# IWatch_DISP.net
KiCad netlist of a schematic drawn in Altium Designer
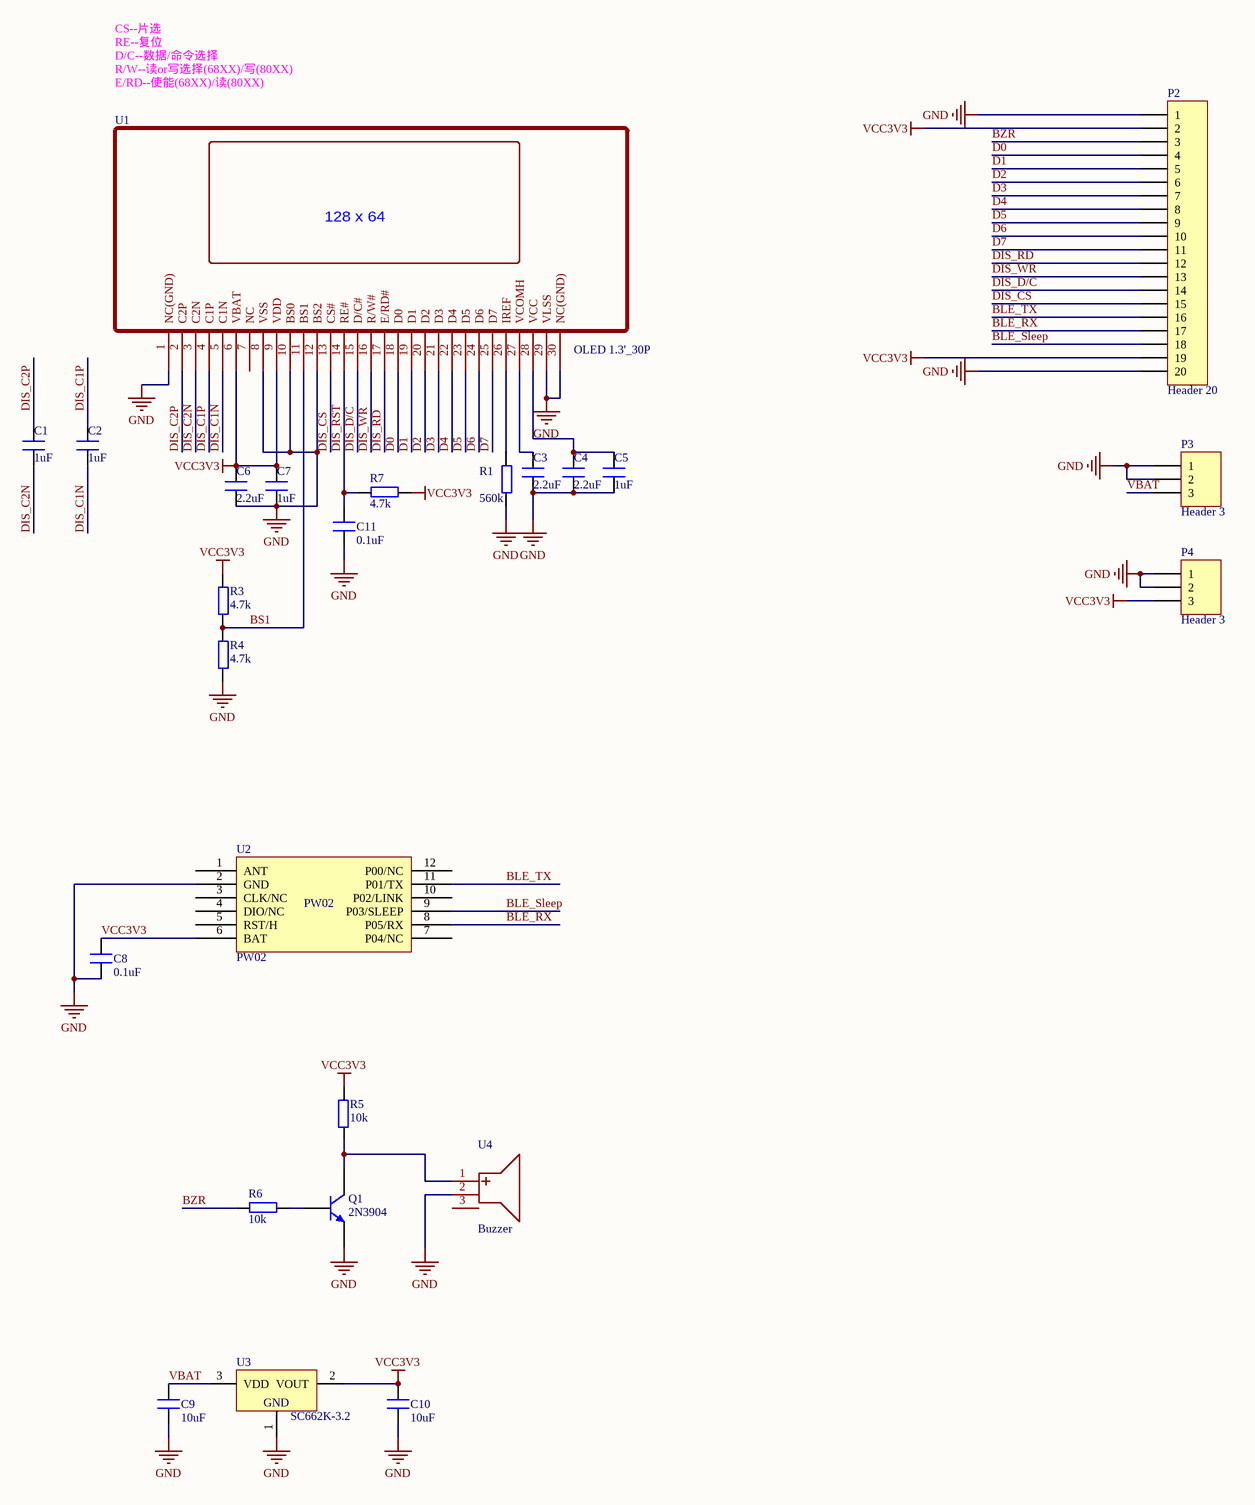
[diagram p0: IWatch_DISP.SchDoc]

(export (version "E")
  (design (tool "Eeschema 10.0.6"))
  (components
    (comp (ref "C1") (value "1uF") (footprint "C0603") (libsource (lib "Explorer STM32F407封装库2") (part "C")))
    (comp (ref "C2") (value "1uF") (footprint "C0603") (libsource (lib "Explorer STM32F407封装库2") (part "C")))
    (comp (ref "C3")
      (value "2.2uF")
      (footprint "C0603")
      (libsource (lib "Explorer STM32F407封装库2") (part "C"))
    )
    (comp (ref "C4")
      (value "2.2uF")
      (footprint "C0603")
      (libsource (lib "Explorer STM32F407封装库2") (part "C"))
    )
    (comp (ref "C5") (value "1uF") (footprint "C0603") (libsource (lib "Explorer STM32F407封装库2") (part "C")))
    (comp (ref "C6")
      (value "2.2uF")
      (footprint "C0603")
      (libsource (lib "Explorer STM32F407封装库2") (part "C"))
    )
    (comp (ref "C7") (value "1uF") (footprint "C0603") (libsource (lib "Explorer STM32F407封装库2") (part "C")))
    (comp (ref "C8")
      (value "0.1uF")
      (footprint "C0603")
      (libsource (lib "Explorer STM32F407封装库2") (part "C"))
    )
    (comp (ref "C9") (value "10uF") (footprint "C0603") (libsource (lib "Explorer STM32F407封装库2") (part "C")))
    (comp (ref "C10")
      (value "10uF")
      (footprint "C0603")
      (libsource (lib "Explorer STM32F407封装库2") (part "C"))
    )
    (comp (ref "C11")
      (value "0.1uF")
      (footprint "C0603")
      (libsource (lib "Explorer STM32F407封装库2") (part "C"))
    )
    (comp (ref "P2")
      (value "Header 20")
      (footprint "HDR_1X20P_1.27MM")
      (description "Header, 20-Pin")
      (fields (field (name "PUBLISHER") "Altium Limited"))
      (libsource (lib "Miscellaneous Connectors") (part "Header 20"))
    )
    (comp (ref "P3")
      (value "Header 3")
      (footprint "HDR_1X3P_1.27MM")
      (description "Header, 3-Pin")
      (fields (field (name "PUBLISHER") "Altium Limited"))
      (libsource (lib "Miscellaneous Connectors") (part "Header 3"))
    )
    (comp (ref "P4")
      (value "Header 3")
      (footprint "HDR_1X3P_1.27MM")
      (description "Header, 3-Pin")
      (fields (field (name "PUBLISHER") "Altium Limited"))
      (libsource (lib "Miscellaneous Connectors") (part "Header 3"))
    )
    (comp (ref "Q1")
      (value "2N3904")
      (footprint "SOT23-3")
      (description "NPN General Purpose Amplifier")
      (fields (field (name "PUBLISHER") "Altium Limited"))
      (libsource (lib "Miscellaneous Devices") (part "2N3904"))
    )
    (comp (ref "R1") (value "560k") (footprint "R0603") (libsource (lib "Explorer STM32F407封装库2") (part "R")))
    (comp (ref "R3") (value "4.7k") (footprint "R0603") (libsource (lib "Explorer STM32F407封装库2") (part "R")))
    (comp (ref "R4") (value "4.7k") (footprint "R0603") (libsource (lib "Explorer STM32F407封装库2") (part "R")))
    (comp (ref "R5") (value "10k") (footprint "R0603") (libsource (lib "Explorer STM32F407封装库2") (part "R")))
    (comp (ref "R6") (value "10k") (footprint "R0603") (libsource (lib "Explorer STM32F407封装库2") (part "R")))
    (comp (ref "R7") (value "4.7k") (footprint "R0603") (libsource (lib "Explorer STM32F407封装库2") (part "R")))
    (comp (ref "U1")
      (value "OLED 1.3'_30P")
      (footprint "OLED 1.3'_30P")
      (description "1.3寸oled显示屏12864 分辨率 驱动芯片ssd1315兼容ssd1306")
      (libsource (lib "TOF_SCH") (part "OLED 1.3'_30P"))
    )
    (comp (ref "U2")
      (value "PW02")
      (footprint "PW02")
      (description "PW02 蓝牙模块 蓝牙5.0 串口透传,DA14585芯片")
      (libsource (lib "IWatch") (part "PW02"))
    )
    (comp (ref "U3")
      (value "SC662K-3.2")
      (footprint "SOT23-3")
      (description "Low Dropout,  250mA")
      (libsource (lib "TOF_SCH") (part "SC662K-3.2"))
    )
    (comp (ref "U4")
      (value "Buzzer")
      (footprint "Buzzer_5.5x2.5mm")
      (libsource (lib "TOF_SCH") (part "Buzzer"))
    )
  )
  (nets
    (net (code "1") (name "/BLE_RX") (class "Default")
      (node (ref "P2") (pin "17") (pinfunction "17_17") (pintype "passive"))
      (node (ref "U2") (pin "8") (pinfunction "P05/RX_8") (pintype "passive"))
    )
    (net (code "2") (name "/BLE_Sleep") (class "Default")
      (node (ref "P2") (pin "18") (pinfunction "18_18") (pintype "passive"))
      (node (ref "U2") (pin "9") (pinfunction "P03/SLEEP_9") (pintype "passive"))
    )
    (net (code "3") (name "/BLE_TX") (class "Default")
      (node (ref "P2") (pin "16") (pinfunction "16_16") (pintype "passive"))
      (node (ref "U2") (pin "11") (pinfunction "P01/TX_11") (pintype "passive"))
    )
    (net (code "4") (name "/BS1") (class "Default")
      (node (ref "R3") (pin "1") (pintype "passive"))
      (node (ref "R4") (pin "2") (pintype "passive"))
      (node (ref "U1") (pin "11") (pinfunction "BS1_11") (pintype "passive"))
    )
    (net (code "5") (name "/BZR") (class "Default")
      (node (ref "P2") (pin "3") (pinfunction "3_3") (pintype "passive"))
      (node (ref "R6") (pin "2") (pintype "passive"))
    )
    (net (code "6") (name "/D0") (class "Default")
      (node (ref "P2") (pin "4") (pinfunction "4_4") (pintype "passive"))
      (node (ref "U1") (pin "18") (pinfunction "D0_18") (pintype "passive"))
    )
    (net (code "7") (name "/D1") (class "Default")
      (node (ref "P2") (pin "5") (pinfunction "5_5") (pintype "passive"))
      (node (ref "U1") (pin "19") (pinfunction "D1_19") (pintype "passive"))
    )
    (net (code "8") (name "/D2") (class "Default")
      (node (ref "P2") (pin "6") (pinfunction "6_6") (pintype "passive"))
      (node (ref "U1") (pin "20") (pinfunction "D2_20") (pintype "passive"))
    )
    (net (code "9") (name "/D3") (class "Default")
      (node (ref "P2") (pin "7") (pinfunction "7_7") (pintype "passive"))
      (node (ref "U1") (pin "21") (pinfunction "D3_21") (pintype "passive"))
    )
    (net (code "10") (name "/D4") (class "Default")
      (node (ref "P2") (pin "8") (pinfunction "8_8") (pintype "passive"))
      (node (ref "U1") (pin "22") (pinfunction "D4_22") (pintype "passive"))
    )
    (net (code "11") (name "/D5") (class "Default")
      (node (ref "P2") (pin "9") (pinfunction "9_9") (pintype "passive"))
      (node (ref "U1") (pin "23") (pinfunction "D5_23") (pintype "passive"))
    )
    (net (code "12") (name "/D6") (class "Default")
      (node (ref "P2") (pin "10") (pinfunction "10_10") (pintype "passive"))
      (node (ref "U1") (pin "24") (pinfunction "D6_24") (pintype "passive"))
    )
    (net (code "13") (name "/D7") (class "Default")
      (node (ref "P2") (pin "11") (pinfunction "11_11") (pintype "passive"))
      (node (ref "U1") (pin "25") (pinfunction "D7_25") (pintype "passive"))
    )
    (net (code "14") (name "/DIS_C1N") (class "Default")
      (node (ref "C2") (pin "1") (pintype "passive"))
      (node (ref "U1") (pin "5") (pinfunction "C1N_5") (pintype "passive"))
    )
    (net (code "15") (name "/DIS_C1P") (class "Default")
      (node (ref "C2") (pin "2") (pintype "passive"))
      (node (ref "U1") (pin "4") (pinfunction "C1P_4") (pintype "passive"))
    )
    (net (code "16") (name "/DIS_C2N") (class "Default")
      (node (ref "C1") (pin "1") (pintype "passive"))
      (node (ref "U1") (pin "3") (pinfunction "C2N_3") (pintype "passive"))
    )
    (net (code "17") (name "/DIS_C2P") (class "Default")
      (node (ref "C1") (pin "2") (pintype "passive"))
      (node (ref "U1") (pin "2") (pinfunction "C2P_2") (pintype "passive"))
    )
    (net (code "18") (name "/DIS_CS") (class "Default")
      (node (ref "P2") (pin "15") (pinfunction "15_15") (pintype "passive"))
      (node (ref "U1") (pin "13") (pinfunction "CS#_13") (pintype "passive"))
    )
    (net (code "19") (name "/DIS_D{slash}C") (class "Default")
      (node (ref "P2") (pin "14") (pinfunction "14_14") (pintype "passive"))
      (node (ref "U1") (pin "15") (pinfunction "D/C#_15") (pintype "passive"))
    )
    (net (code "20") (name "/DIS_RD") (class "Default")
      (node (ref "P2") (pin "12") (pinfunction "12_12") (pintype "passive"))
      (node (ref "U1") (pin "17") (pinfunction "E/RD#_17") (pintype "passive"))
    )
    (net (code "21") (name "/DIS_RST") (class "Default")
      (node (ref "C11") (pin "2") (pintype "passive"))
      (node (ref "R7") (pin "2") (pintype "passive"))
      (node (ref "U1") (pin "14") (pinfunction "RE#_14") (pintype "passive"))
    )
    (net (code "22") (name "/DIS_WR") (class "Default")
      (node (ref "P2") (pin "13") (pinfunction "13_13") (pintype "passive"))
      (node (ref "U1") (pin "16") (pinfunction "R/W#_16") (pintype "passive"))
    )
    (net (code "23") (name "/VBAT") (class "Default")
      (node (ref "C9") (pin "2") (pintype "passive"))
      (node (ref "P3") (pin "3") (pinfunction "3_3") (pintype "passive"))
      (node (ref "U3") (pin "3") (pinfunction "VDD_3") (pintype "passive"))
    )
    (net (code "24") (name "GND") (class "Default")
      (node (ref "C10") (pin "1") (pintype "passive"))
      (node (ref "C11") (pin "1") (pintype "passive"))
      (node (ref "C3") (pin "1") (pintype "passive"))
      (node (ref "C4") (pin "1") (pintype "passive"))
      (node (ref "C5") (pin "1") (pintype "passive"))
      (node (ref "C6") (pin "1") (pintype "passive"))
      (node (ref "C7") (pin "1") (pintype "passive"))
      (node (ref "C8") (pin "1") (pintype "passive"))
      (node (ref "C9") (pin "1") (pintype "passive"))
      (node (ref "P2") (pin "1") (pinfunction "1_1") (pintype "passive"))
      (node (ref "P2") (pin "20") (pinfunction "20_20") (pintype "passive"))
      (node (ref "P3") (pin "1") (pinfunction "1_1") (pintype "passive"))
      (node (ref "P3") (pin "2") (pinfunction "2_2") (pintype "passive"))
      (node (ref "P4") (pin "1") (pinfunction "1_1") (pintype "passive"))
      (node (ref "P4") (pin "2") (pinfunction "2_2") (pintype "passive"))
      (node (ref "Q1") (pin "1") (pinfunction "E_1") (pintype "passive"))
      (node (ref "R1") (pin "1") (pintype "passive"))
      (node (ref "R4") (pin "1") (pintype "passive"))
      (node (ref "U1") (pin "1") (pinfunction "NC(GND)_1") (pintype "passive"))
      (node (ref "U1") (pin "10") (pinfunction "BS0_10") (pintype "passive"))
      (node (ref "U1") (pin "12") (pinfunction "BS2_12") (pintype "passive"))
      (node (ref "U1") (pin "29") (pinfunction "VLSS_29") (pintype "passive"))
      (node (ref "U1") (pin "30") (pinfunction "NC(GND)_30") (pintype "passive"))
      (node (ref "U1") (pin "8") (pinfunction "VSS_8") (pintype "passive"))
      (node (ref "U2") (pin "2") (pinfunction "GND_2") (pintype "passive"))
      (node (ref "U3") (pin "1") (pinfunction "GND_1") (pintype "passive"))
      (node (ref "U4") (pin "2") (pinfunction "-_2") (pintype "passive"))
    )
    (net (code "25") (name "Net-(Q1-B)") (class "Default")
      (node (ref "Q1") (pin "2") (pinfunction "B_2") (pintype "passive"))
      (node (ref "R6") (pin "1") (pintype "passive"))
    )
    (net (code "26") (name "Net-(Q1-C)") (class "Default")
      (node (ref "Q1") (pin "3") (pinfunction "C_3") (pintype "passive"))
      (node (ref "R5") (pin "2") (pintype "passive"))
      (node (ref "U4") (pin "1") (pinfunction "+_1") (pintype "passive"))
    )
    (net (code "27") (name "Net-(U1-IREF)") (class "Default")
      (node (ref "R1") (pin "2") (pintype "passive"))
      (node (ref "U1") (pin "26") (pinfunction "IREF_26") (pintype "passive"))
    )
    (net (code "28") (name "Net-(U1-VCC)") (class "Default")
      (node (ref "C4") (pin "2") (pintype "passive"))
      (node (ref "C5") (pin "2") (pintype "passive"))
      (node (ref "U1") (pin "28") (pinfunction "VCC_28") (pintype "passive"))
    )
    (net (code "29") (name "Net-(U1-VCOMH)") (class "Default")
      (node (ref "C3") (pin "2") (pintype "passive"))
      (node (ref "U1") (pin "27") (pinfunction "VCOMH_27") (pintype "passive"))
    )
    (net (code "30") (name "VCC3V3") (class "Default")
      (node (ref "C10") (pin "2") (pintype "passive"))
      (node (ref "C6") (pin "2") (pintype "passive"))
      (node (ref "C7") (pin "2") (pintype "passive"))
      (node (ref "C8") (pin "2") (pintype "passive"))
      (node (ref "P2") (pin "19") (pinfunction "19_19") (pintype "passive"))
      (node (ref "P2") (pin "2") (pinfunction "2_2") (pintype "passive"))
      (node (ref "P4") (pin "3") (pinfunction "3_3") (pintype "passive"))
      (node (ref "R3") (pin "2") (pintype "passive"))
      (node (ref "R5") (pin "1") (pintype "passive"))
      (node (ref "R7") (pin "1") (pintype "passive"))
      (node (ref "U1") (pin "6") (pinfunction "VBAT_6") (pintype "passive"))
      (node (ref "U1") (pin "9") (pinfunction "VDD_9") (pintype "passive"))
      (node (ref "U2") (pin "6") (pinfunction "BAT_6") (pintype "passive"))
      (node (ref "U3") (pin "2") (pinfunction "VOUT_2") (pintype "passive"))
    )
    (net (code "31") (name "unconnected-(U1-NC-Pad7)") (class "Default")
      (node (ref "U1") (pin "7") (pinfunction "NC_7") (pintype "passive"))
    )
    (net (code "32") (name "unconnected-(U2-ANT-Pad1)") (class "Default")
      (node (ref "U2") (pin "1") (pinfunction "ANT_1") (pintype "passive"))
    )
    (net (code "33") (name "unconnected-(U2-CLK{slash}NC-Pad3)") (class "Default")
      (node (ref "U2") (pin "3") (pinfunction "CLK/NC_3") (pintype "passive"))
    )
    (net (code "34") (name "unconnected-(U2-DIO{slash}NC-Pad4)") (class "Default")
      (node (ref "U2") (pin "4") (pinfunction "DIO/NC_4") (pintype "passive"))
    )
    (net (code "35") (name "unconnected-(U2-P00{slash}NC-Pad12)") (class "Default")
      (node (ref "U2") (pin "12") (pinfunction "P00/NC_12") (pintype "passive"))
    )
    (net (code "36") (name "unconnected-(U2-P02{slash}LINK-Pad10)") (class "Default")
      (node (ref "U2") (pin "10") (pinfunction "P02/LINK_10") (pintype "passive"))
    )
    (net (code "37") (name "unconnected-(U2-P04{slash}NC-Pad7)") (class "Default")
      (node (ref "U2") (pin "7") (pinfunction "P04/NC_7") (pintype "passive"))
    )
    (net (code "38") (name "unconnected-(U2-RST{slash}H-Pad5)") (class "Default")
      (node (ref "U2") (pin "5") (pinfunction "RST/H_5") (pintype "passive"))
    )
    (net (code "39") (name "unconnected-(U4-Pad3)") (class "Default")
      (node (ref "U4") (pin "3") (pinfunction "3_3") (pintype "passive"))
    )
  )
)
